# 3V3_LDO.net
KiCad netlist of a schematic drawn in Altium Designer
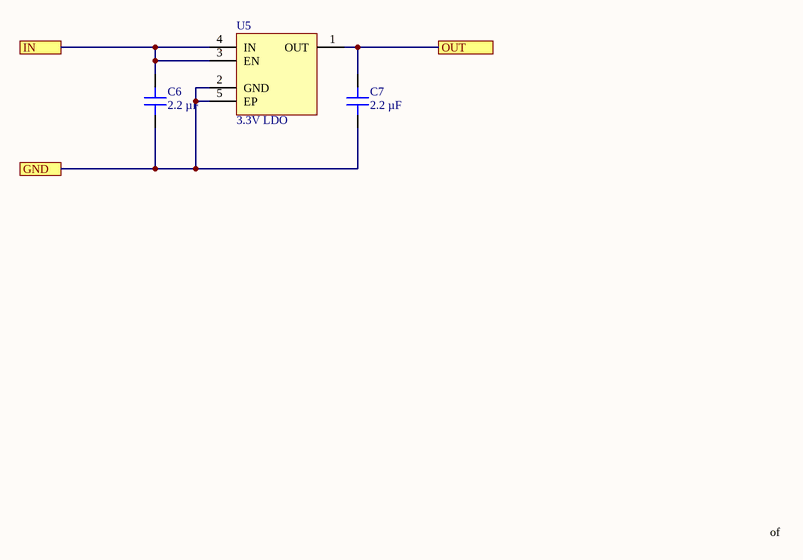
[diagram p0: 3V3_LDO.SchDoc]

(export (version "E")
  (design (tool "Eeschema 10.0.6"))
  (components
    (comp (ref "C6")
      (value "2.2 µF")
      (footprint "CAP 0201_0603")
      (description "CAP CER 0.1UF 35V X5R 0201")
      (fields
        (field (name "PART NUMBER") "GRT033R6YA104KE01D")
        (field (name "MANUFACTURER") "Murata Electronics")
      )
      (libsource (lib "Celestial Altium Library - altium_library") (part "Capacitor"))
    )
    (comp (ref "C7")
      (value "2.2 µF")
      (footprint "CAP 0201_0603")
      (description "CAP CER 0.1UF 35V X5R 0201")
      (fields
        (field (name "PART NUMBER") "GRT033R6YA104KE01D")
        (field (name "MANUFACTURER") "Murata Electronics")
      )
      (libsource (lib "Celestial Altium Library - altium_library") (part "Capacitor"))
    )
    (comp (ref "U5") (value "3.3V LDO") (footprint "XDFN-4") (libsource (lib "IC") (part "TLV74033PDQNR")))
  )
  (nets
    (net (code "1") (name "/GND") (class "Default")
      (node (ref "C6") (pin "2") (pinfunction "2_2") (pintype "passive"))
      (node (ref "C7") (pin "2") (pinfunction "2_2") (pintype "passive"))
      (node (ref "U5") (pin "2") (pinfunction "GND_2") (pintype "passive"))
      (node (ref "U5") (pin "5") (pinfunction "EP_5") (pintype "passive"))
    )
    (net (code "2") (name "/IN") (class "Default")
      (node (ref "C6") (pin "1") (pinfunction "1_1") (pintype "passive"))
      (node (ref "U5") (pin "3") (pinfunction "EN_3") (pintype "passive"))
      (node (ref "U5") (pin "4") (pinfunction "IN_4") (pintype "passive"))
    )
    (net (code "3") (name "/OUT") (class "Default")
      (node (ref "C7") (pin "1") (pinfunction "1_1") (pintype "passive"))
      (node (ref "U5") (pin "1") (pinfunction "OUT_1") (pintype "passive"))
    )
  )
)
